# SolarArray1.net
KiCad netlist of a schematic drawn in Altium Designer
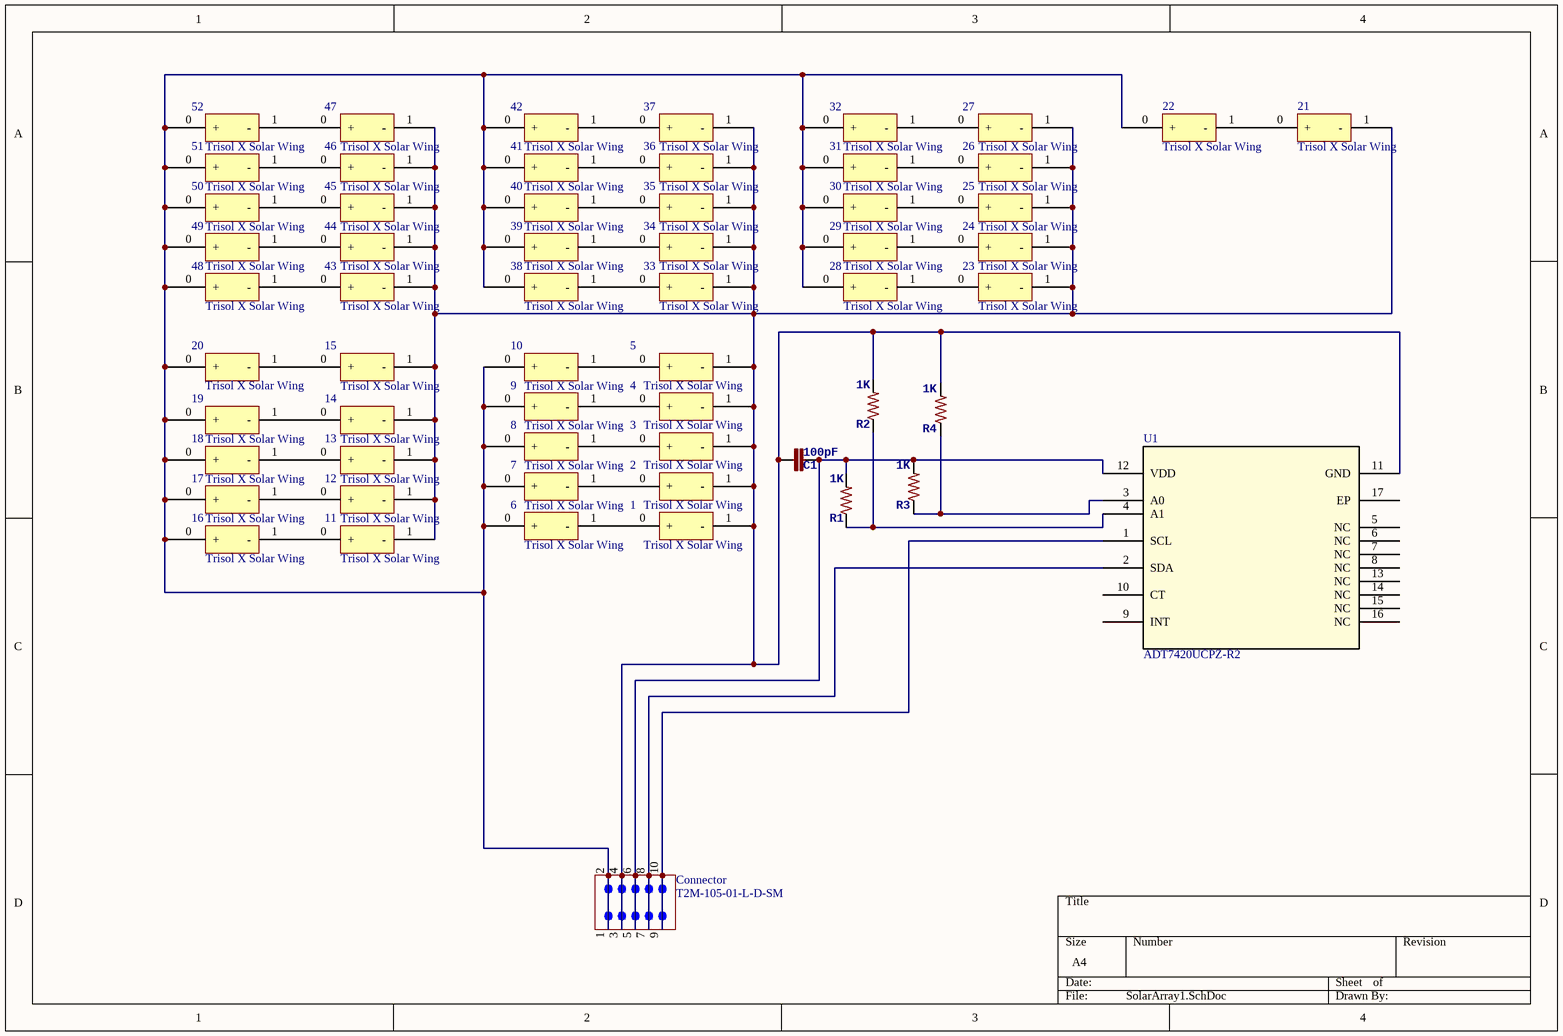
[diagram p0: SolarArray1.SchDoc]

(export (version "E")
  (design (tool "Eeschema 10.0.6"))
  (components
    (comp (ref "1")
      (value "Trisol X Solar Wing")
      (footprint "PCBComponent_1")
      (libsource (lib "CSDCPowerLib") (part "Trisol X Solar Wing"))
    )
    (comp (ref "2")
      (value "Trisol X Solar Wing")
      (footprint "PCBComponent_1")
      (libsource (lib "CSDCPowerLib") (part "Trisol X Solar Wing"))
    )
    (comp (ref "3")
      (value "Trisol X Solar Wing")
      (footprint "PCBComponent_1")
      (libsource (lib "CSDCPowerLib") (part "Trisol X Solar Wing"))
    )
    (comp (ref "4")
      (value "Trisol X Solar Wing")
      (footprint "PCBComponent_1")
      (libsource (lib "CSDCPowerLib") (part "Trisol X Solar Wing"))
    )
    (comp (ref "5")
      (value "Trisol X Solar Wing")
      (footprint "PCBComponent_1")
      (libsource (lib "CSDCPowerLib") (part "Trisol X Solar Wing"))
    )
    (comp (ref "6")
      (value "Trisol X Solar Wing")
      (footprint "PCBComponent_1")
      (libsource (lib "CSDCPowerLib") (part "Trisol X Solar Wing"))
    )
    (comp (ref "7")
      (value "Trisol X Solar Wing")
      (footprint "PCBComponent_1")
      (libsource (lib "CSDCPowerLib") (part "Trisol X Solar Wing"))
    )
    (comp (ref "8")
      (value "Trisol X Solar Wing")
      (footprint "PCBComponent_1")
      (libsource (lib "CSDCPowerLib") (part "Trisol X Solar Wing"))
    )
    (comp (ref "9")
      (value "Trisol X Solar Wing")
      (footprint "PCBComponent_1")
      (libsource (lib "CSDCPowerLib") (part "Trisol X Solar Wing"))
    )
    (comp (ref "10")
      (value "Trisol X Solar Wing")
      (footprint "PCBComponent_1")
      (libsource (lib "CSDCPowerLib") (part "Trisol X Solar Wing"))
    )
    (comp (ref "11")
      (value "Trisol X Solar Wing")
      (footprint "PCBComponent_1")
      (libsource (lib "CSDCPowerLib") (part "Trisol X Solar Wing"))
    )
    (comp (ref "12")
      (value "Trisol X Solar Wing")
      (footprint "PCBComponent_1")
      (libsource (lib "CSDCPowerLib") (part "Trisol X Solar Wing"))
    )
    (comp (ref "13")
      (value "Trisol X Solar Wing")
      (footprint "PCBComponent_1")
      (libsource (lib "CSDCPowerLib") (part "Trisol X Solar Wing"))
    )
    (comp (ref "14")
      (value "Trisol X Solar Wing")
      (footprint "PCBComponent_1")
      (libsource (lib "CSDCPowerLib") (part "Trisol X Solar Wing"))
    )
    (comp (ref "15")
      (value "Trisol X Solar Wing")
      (footprint "PCBComponent_1")
      (libsource (lib "CSDCPowerLib") (part "Trisol X Solar Wing"))
    )
    (comp (ref "16")
      (value "Trisol X Solar Wing")
      (footprint "PCBComponent_1")
      (libsource (lib "CSDCPowerLib") (part "Trisol X Solar Wing"))
    )
    (comp (ref "17")
      (value "Trisol X Solar Wing")
      (footprint "PCBComponent_1")
      (libsource (lib "CSDCPowerLib") (part "Trisol X Solar Wing"))
    )
    (comp (ref "18")
      (value "Trisol X Solar Wing")
      (footprint "PCBComponent_1")
      (libsource (lib "CSDCPowerLib") (part "Trisol X Solar Wing"))
    )
    (comp (ref "19")
      (value "Trisol X Solar Wing")
      (footprint "PCBComponent_1")
      (libsource (lib "CSDCPowerLib") (part "Trisol X Solar Wing"))
    )
    (comp (ref "20")
      (value "Trisol X Solar Wing")
      (footprint "PCBComponent_1")
      (libsource (lib "CSDCPowerLib") (part "Trisol X Solar Wing"))
    )
    (comp (ref "21")
      (value "Trisol X Solar Wing")
      (footprint "PCBComponent_1")
      (libsource (lib "CSDCPowerLib") (part "Trisol X Solar Wing"))
    )
    (comp (ref "22")
      (value "Trisol X Solar Wing")
      (footprint "PCBComponent_1")
      (libsource (lib "CSDCPowerLib") (part "Trisol X Solar Wing"))
    )
    (comp (ref "23")
      (value "Trisol X Solar Wing")
      (footprint "PCBComponent_1")
      (libsource (lib "CSDCPowerLib") (part "Trisol X Solar Wing"))
    )
    (comp (ref "24")
      (value "Trisol X Solar Wing")
      (footprint "PCBComponent_1")
      (libsource (lib "CSDCPowerLib") (part "Trisol X Solar Wing"))
    )
    (comp (ref "25")
      (value "Trisol X Solar Wing")
      (footprint "PCBComponent_1")
      (libsource (lib "CSDCPowerLib") (part "Trisol X Solar Wing"))
    )
    (comp (ref "26")
      (value "Trisol X Solar Wing")
      (footprint "PCBComponent_1")
      (libsource (lib "CSDCPowerLib") (part "Trisol X Solar Wing"))
    )
    (comp (ref "27")
      (value "Trisol X Solar Wing")
      (footprint "PCBComponent_1")
      (libsource (lib "CSDCPowerLib") (part "Trisol X Solar Wing"))
    )
    (comp (ref "28")
      (value "Trisol X Solar Wing")
      (footprint "PCBComponent_1")
      (libsource (lib "CSDCPowerLib") (part "Trisol X Solar Wing"))
    )
    (comp (ref "29")
      (value "Trisol X Solar Wing")
      (footprint "PCBComponent_1")
      (libsource (lib "CSDCPowerLib") (part "Trisol X Solar Wing"))
    )
    (comp (ref "30")
      (value "Trisol X Solar Wing")
      (footprint "PCBComponent_1")
      (libsource (lib "CSDCPowerLib") (part "Trisol X Solar Wing"))
    )
    (comp (ref "31")
      (value "Trisol X Solar Wing")
      (footprint "PCBComponent_1")
      (libsource (lib "CSDCPowerLib") (part "Trisol X Solar Wing"))
    )
    (comp (ref "32")
      (value "Trisol X Solar Wing")
      (footprint "PCBComponent_1")
      (libsource (lib "CSDCPowerLib") (part "Trisol X Solar Wing"))
    )
    (comp (ref "33")
      (value "Trisol X Solar Wing")
      (footprint "PCBComponent_1")
      (libsource (lib "CSDCPowerLib") (part "Trisol X Solar Wing"))
    )
    (comp (ref "34")
      (value "Trisol X Solar Wing")
      (footprint "PCBComponent_1")
      (libsource (lib "CSDCPowerLib") (part "Trisol X Solar Wing"))
    )
    (comp (ref "35")
      (value "Trisol X Solar Wing")
      (footprint "PCBComponent_1")
      (libsource (lib "CSDCPowerLib") (part "Trisol X Solar Wing"))
    )
    (comp (ref "36")
      (value "Trisol X Solar Wing")
      (footprint "PCBComponent_1")
      (libsource (lib "CSDCPowerLib") (part "Trisol X Solar Wing"))
    )
    (comp (ref "37")
      (value "Trisol X Solar Wing")
      (footprint "PCBComponent_1")
      (libsource (lib "CSDCPowerLib") (part "Trisol X Solar Wing"))
    )
    (comp (ref "38")
      (value "Trisol X Solar Wing")
      (footprint "PCBComponent_1")
      (libsource (lib "CSDCPowerLib") (part "Trisol X Solar Wing"))
    )
    (comp (ref "39")
      (value "Trisol X Solar Wing")
      (footprint "PCBComponent_1")
      (libsource (lib "CSDCPowerLib") (part "Trisol X Solar Wing"))
    )
    (comp (ref "40")
      (value "Trisol X Solar Wing")
      (footprint "PCBComponent_1")
      (libsource (lib "CSDCPowerLib") (part "Trisol X Solar Wing"))
    )
    (comp (ref "41")
      (value "Trisol X Solar Wing")
      (footprint "PCBComponent_1")
      (libsource (lib "CSDCPowerLib") (part "Trisol X Solar Wing"))
    )
    (comp (ref "42")
      (value "Trisol X Solar Wing")
      (footprint "PCBComponent_1")
      (libsource (lib "CSDCPowerLib") (part "Trisol X Solar Wing"))
    )
    (comp (ref "43")
      (value "Trisol X Solar Wing")
      (footprint "PCBComponent_1")
      (libsource (lib "CSDCPowerLib") (part "Trisol X Solar Wing"))
    )
    (comp (ref "44")
      (value "Trisol X Solar Wing")
      (footprint "PCBComponent_1")
      (libsource (lib "CSDCPowerLib") (part "Trisol X Solar Wing"))
    )
    (comp (ref "45")
      (value "Trisol X Solar Wing")
      (footprint "PCBComponent_1")
      (libsource (lib "CSDCPowerLib") (part "Trisol X Solar Wing"))
    )
    (comp (ref "46")
      (value "Trisol X Solar Wing")
      (footprint "PCBComponent_1")
      (libsource (lib "CSDCPowerLib") (part "Trisol X Solar Wing"))
    )
    (comp (ref "47")
      (value "Trisol X Solar Wing")
      (footprint "PCBComponent_1")
      (libsource (lib "CSDCPowerLib") (part "Trisol X Solar Wing"))
    )
    (comp (ref "48")
      (value "Trisol X Solar Wing")
      (footprint "PCBComponent_1")
      (libsource (lib "CSDCPowerLib") (part "Trisol X Solar Wing"))
    )
    (comp (ref "49")
      (value "Trisol X Solar Wing")
      (footprint "PCBComponent_1")
      (libsource (lib "CSDCPowerLib") (part "Trisol X Solar Wing"))
    )
    (comp (ref "50")
      (value "Trisol X Solar Wing")
      (footprint "PCBComponent_1")
      (libsource (lib "CSDCPowerLib") (part "Trisol X Solar Wing"))
    )
    (comp (ref "51")
      (value "Trisol X Solar Wing")
      (footprint "PCBComponent_1")
      (libsource (lib "CSDCPowerLib") (part "Trisol X Solar Wing"))
    )
    (comp (ref "52")
      (value "Trisol X Solar Wing")
      (footprint "PCBComponent_1")
      (libsource (lib "CSDCPowerLib") (part "Trisol X Solar Wing"))
    )
    (comp (ref "C1")
      (value "100pF")
      (footprint "0805")
      (fields (field (name "TOLERANCE") "±10%"))
      (libsource (lib "yusend_power") (part "CAP0805_1nF"))
    )
    (comp (ref "Connector")
      (value "T2M-105-01-L-D-SM")
      (footprint "T2M-105-01-X-D-SM")
      (libsource (lib "CSDCPowerLib") (part "T2M-105-01-X-D-SM"))
    )
    (comp (ref "R1")
      (value "1K")
      (footprint "0805")
      (fields
        (field (name "MANUFACTURER") "TE Connectivity")
        (field (name "MANUFACTURER PART NUMBER") "1625856-2")
        (field (name "TOLERANCE") "±10%")
      )
      (libsource (lib "yusend_power") (part "RESISTOR0805-RES_1K"))
    )
    (comp (ref "R2")
      (value "1K")
      (footprint "0805")
      (fields
        (field (name "MANUFACTURER") "TE Connectivity")
        (field (name "MANUFACTURER PART NUMBER") "1625856-2")
        (field (name "TOLERANCE") "±10%")
      )
      (libsource (lib "yusend_power") (part "RESISTOR0805-RES_1K"))
    )
    (comp (ref "R3")
      (value "1K")
      (footprint "0805")
      (fields
        (field (name "MANUFACTURER") "TE Connectivity")
        (field (name "MANUFACTURER PART NUMBER") "1625856-2")
        (field (name "TOLERANCE") "±10%")
      )
      (libsource (lib "yusend_power") (part "RESISTOR0805-RES_1K"))
    )
    (comp (ref "R4")
      (value "1K")
      (footprint "0805")
      (fields
        (field (name "MANUFACTURER") "TE Connectivity")
        (field (name "MANUFACTURER PART NUMBER") "1625856-2")
        (field (name "TOLERANCE") "±10%")
      )
      (libsource (lib "yusend_power") (part "RESISTOR0805-RES_1K"))
    )
    (comp (ref "U1")
      (value "ADT7420UCPZ-R2")
      (footprint "CP_16_17")
      (description "Imported")
      (libsource (lib "Temperature sensor") (part "ADT7420UCPZ-R2"))
    )
  )
  (nets
    (net (code "1") (name "Net-(1-+)") (class "Default")
      (node (ref "1") (pin "0") (pinfunction "+_0") (pintype "passive"))
      (node (ref "6") (pin "1") (pinfunction "-_1") (pintype "passive"))
    )
    (net (code "2") (name "Net-(1--)") (class "Default")
      (node (ref "1") (pin "1") (pinfunction "-_1") (pintype "passive"))
      (node (ref "11") (pin "1") (pinfunction "-_1") (pintype "passive"))
      (node (ref "12") (pin "1") (pinfunction "-_1") (pintype "passive"))
      (node (ref "13") (pin "1") (pinfunction "-_1") (pintype "passive"))
      (node (ref "14") (pin "1") (pinfunction "-_1") (pintype "passive"))
      (node (ref "15") (pin "1") (pinfunction "-_1") (pintype "passive"))
      (node (ref "2") (pin "1") (pinfunction "-_1") (pintype "passive"))
      (node (ref "21") (pin "1") (pinfunction "-_1") (pintype "passive"))
      (node (ref "23") (pin "1") (pinfunction "-_1") (pintype "passive"))
      (node (ref "24") (pin "1") (pinfunction "-_1") (pintype "passive"))
      (node (ref "25") (pin "1") (pinfunction "-_1") (pintype "passive"))
      (node (ref "26") (pin "1") (pinfunction "-_1") (pintype "passive"))
      (node (ref "27") (pin "1") (pinfunction "-_1") (pintype "passive"))
      (node (ref "3") (pin "1") (pinfunction "-_1") (pintype "passive"))
      (node (ref "33") (pin "1") (pinfunction "-_1") (pintype "passive"))
      (node (ref "34") (pin "1") (pinfunction "-_1") (pintype "passive"))
      (node (ref "35") (pin "1") (pinfunction "-_1") (pintype "passive"))
      (node (ref "36") (pin "1") (pinfunction "-_1") (pintype "passive"))
      (node (ref "37") (pin "1") (pinfunction "-_1") (pintype "passive"))
      (node (ref "4") (pin "1") (pinfunction "-_1") (pintype "passive"))
      (node (ref "43") (pin "1") (pinfunction "-_1") (pintype "passive"))
      (node (ref "44") (pin "1") (pinfunction "-_1") (pintype "passive"))
      (node (ref "45") (pin "1") (pinfunction "-_1") (pintype "passive"))
      (node (ref "46") (pin "1") (pinfunction "-_1") (pintype "passive"))
      (node (ref "47") (pin "1") (pinfunction "-_1") (pintype "passive"))
      (node (ref "5") (pin "1") (pinfunction "-_1") (pintype "passive"))
      (node (ref "C1") (pin "1") (pinfunction "1_1") (pintype "passive"))
      (node (ref "Connector") (pin "3") (pinfunction "PINLENGTH=20_3") (pintype "passive"))
      (node (ref "Connector") (pin "4") (pinfunction "PINLENGTH=20_4") (pintype "passive"))
      (node (ref "R2") (pin "2") (pinfunction "2_2") (pintype "passive"))
      (node (ref "R4") (pin "2") (pinfunction "2_2") (pintype "passive"))
      (node (ref "U1") (pin "11") (pinfunction "GND_11") (pintype "passive"))
    )
    (net (code "3") (name "Net-(2-+)") (class "Default")
      (node (ref "2") (pin "0") (pinfunction "+_0") (pintype "passive"))
      (node (ref "7") (pin "1") (pinfunction "-_1") (pintype "passive"))
    )
    (net (code "4") (name "Net-(3-+)") (class "Default")
      (node (ref "3") (pin "0") (pinfunction "+_0") (pintype "passive"))
      (node (ref "8") (pin "1") (pinfunction "-_1") (pintype "passive"))
    )
    (net (code "5") (name "Net-(4-+)") (class "Default")
      (node (ref "4") (pin "0") (pinfunction "+_0") (pintype "passive"))
      (node (ref "9") (pin "1") (pinfunction "-_1") (pintype "passive"))
    )
    (net (code "6") (name "Net-(10-+)") (class "Default")
      (node (ref "10") (pin "0") (pinfunction "+_0") (pintype "passive"))
      (node (ref "16") (pin "0") (pinfunction "+_0") (pintype "passive"))
      (node (ref "17") (pin "0") (pinfunction "+_0") (pintype "passive"))
      (node (ref "18") (pin "0") (pinfunction "+_0") (pintype "passive"))
      (node (ref "19") (pin "0") (pinfunction "+_0") (pintype "passive"))
      (node (ref "20") (pin "0") (pinfunction "+_0") (pintype "passive"))
      (node (ref "22") (pin "0") (pinfunction "+_0") (pintype "passive"))
      (node (ref "28") (pin "0") (pinfunction "+_0") (pintype "passive"))
      (node (ref "29") (pin "0") (pinfunction "+_0") (pintype "passive"))
      (node (ref "30") (pin "0") (pinfunction "+_0") (pintype "passive"))
      (node (ref "31") (pin "0") (pinfunction "+_0") (pintype "passive"))
      (node (ref "32") (pin "0") (pinfunction "+_0") (pintype "passive"))
      (node (ref "38") (pin "0") (pinfunction "+_0") (pintype "passive"))
      (node (ref "39") (pin "0") (pinfunction "+_0") (pintype "passive"))
      (node (ref "40") (pin "0") (pinfunction "+_0") (pintype "passive"))
      (node (ref "41") (pin "0") (pinfunction "+_0") (pintype "passive"))
      (node (ref "42") (pin "0") (pinfunction "+_0") (pintype "passive"))
      (node (ref "48") (pin "0") (pinfunction "+_0") (pintype "passive"))
      (node (ref "49") (pin "0") (pinfunction "+_0") (pintype "passive"))
      (node (ref "50") (pin "0") (pinfunction "+_0") (pintype "passive"))
      (node (ref "51") (pin "0") (pinfunction "+_0") (pintype "passive"))
      (node (ref "52") (pin "0") (pinfunction "+_0") (pintype "passive"))
      (node (ref "6") (pin "0") (pinfunction "+_0") (pintype "passive"))
      (node (ref "7") (pin "0") (pinfunction "+_0") (pintype "passive"))
      (node (ref "8") (pin "0") (pinfunction "+_0") (pintype "passive"))
      (node (ref "9") (pin "0") (pinfunction "+_0") (pintype "passive"))
      (node (ref "Connector") (pin "1") (pinfunction "PINLENGTH=20_1") (pintype "passive"))
      (node (ref "Connector") (pin "2") (pinfunction "PINLENGTH=20_2") (pintype "passive"))
    )
    (net (code "7") (name "Net-(10--)") (class "Default")
      (node (ref "10") (pin "1") (pinfunction "-_1") (pintype "passive"))
      (node (ref "5") (pin "0") (pinfunction "+_0") (pintype "passive"))
    )
    (net (code "8") (name "Net-(11-+)") (class "Default")
      (node (ref "11") (pin "0") (pinfunction "+_0") (pintype "passive"))
      (node (ref "16") (pin "1") (pinfunction "-_1") (pintype "passive"))
    )
    (net (code "9") (name "Net-(12-+)") (class "Default")
      (node (ref "12") (pin "0") (pinfunction "+_0") (pintype "passive"))
      (node (ref "17") (pin "1") (pinfunction "-_1") (pintype "passive"))
    )
    (net (code "10") (name "Net-(13-+)") (class "Default")
      (node (ref "13") (pin "0") (pinfunction "+_0") (pintype "passive"))
      (node (ref "18") (pin "1") (pinfunction "-_1") (pintype "passive"))
    )
    (net (code "11") (name "Net-(14-+)") (class "Default")
      (node (ref "14") (pin "0") (pinfunction "+_0") (pintype "passive"))
      (node (ref "19") (pin "1") (pinfunction "-_1") (pintype "passive"))
    )
    (net (code "12") (name "Net-(15-+)") (class "Default")
      (node (ref "15") (pin "0") (pinfunction "+_0") (pintype "passive"))
      (node (ref "20") (pin "1") (pinfunction "-_1") (pintype "passive"))
    )
    (net (code "13") (name "Net-(21-+)") (class "Default")
      (node (ref "21") (pin "0") (pinfunction "+_0") (pintype "passive"))
      (node (ref "22") (pin "1") (pinfunction "-_1") (pintype "passive"))
    )
    (net (code "14") (name "Net-(23-+)") (class "Default")
      (node (ref "23") (pin "0") (pinfunction "+_0") (pintype "passive"))
      (node (ref "28") (pin "1") (pinfunction "-_1") (pintype "passive"))
    )
    (net (code "15") (name "Net-(24-+)") (class "Default")
      (node (ref "24") (pin "0") (pinfunction "+_0") (pintype "passive"))
      (node (ref "29") (pin "1") (pinfunction "-_1") (pintype "passive"))
    )
    (net (code "16") (name "Net-(25-+)") (class "Default")
      (node (ref "25") (pin "0") (pinfunction "+_0") (pintype "passive"))
      (node (ref "30") (pin "1") (pinfunction "-_1") (pintype "passive"))
    )
    (net (code "17") (name "Net-(26-+)") (class "Default")
      (node (ref "26") (pin "0") (pinfunction "+_0") (pintype "passive"))
      (node (ref "31") (pin "1") (pinfunction "-_1") (pintype "passive"))
    )
    (net (code "18") (name "Net-(27-+)") (class "Default")
      (node (ref "27") (pin "0") (pinfunction "+_0") (pintype "passive"))
      (node (ref "32") (pin "1") (pinfunction "-_1") (pintype "passive"))
    )
    (net (code "19") (name "Net-(33-+)") (class "Default")
      (node (ref "33") (pin "0") (pinfunction "+_0") (pintype "passive"))
      (node (ref "38") (pin "1") (pinfunction "-_1") (pintype "passive"))
    )
    (net (code "20") (name "Net-(34-+)") (class "Default")
      (node (ref "34") (pin "0") (pinfunction "+_0") (pintype "passive"))
      (node (ref "39") (pin "1") (pinfunction "-_1") (pintype "passive"))
    )
    (net (code "21") (name "Net-(35-+)") (class "Default")
      (node (ref "35") (pin "0") (pinfunction "+_0") (pintype "passive"))
      (node (ref "40") (pin "1") (pinfunction "-_1") (pintype "passive"))
    )
    (net (code "22") (name "Net-(36-+)") (class "Default")
      (node (ref "36") (pin "0") (pinfunction "+_0") (pintype "passive"))
      (node (ref "41") (pin "1") (pinfunction "-_1") (pintype "passive"))
    )
    (net (code "23") (name "Net-(37-+)") (class "Default")
      (node (ref "37") (pin "0") (pinfunction "+_0") (pintype "passive"))
      (node (ref "42") (pin "1") (pinfunction "-_1") (pintype "passive"))
    )
    (net (code "24") (name "Net-(43-+)") (class "Default")
      (node (ref "43") (pin "0") (pinfunction "+_0") (pintype "passive"))
      (node (ref "48") (pin "1") (pinfunction "-_1") (pintype "passive"))
    )
    (net (code "25") (name "Net-(44-+)") (class "Default")
      (node (ref "44") (pin "0") (pinfunction "+_0") (pintype "passive"))
      (node (ref "49") (pin "1") (pinfunction "-_1") (pintype "passive"))
    )
    (net (code "26") (name "Net-(45-+)") (class "Default")
      (node (ref "45") (pin "0") (pinfunction "+_0") (pintype "passive"))
      (node (ref "50") (pin "1") (pinfunction "-_1") (pintype "passive"))
    )
    (net (code "27") (name "Net-(46-+)") (class "Default")
      (node (ref "46") (pin "0") (pinfunction "+_0") (pintype "passive"))
      (node (ref "51") (pin "1") (pinfunction "-_1") (pintype "passive"))
    )
    (net (code "28") (name "Net-(47-+)") (class "Default")
      (node (ref "47") (pin "0") (pinfunction "+_0") (pintype "passive"))
      (node (ref "52") (pin "1") (pinfunction "-_1") (pintype "passive"))
    )
    (net (code "29") (name "Net-(U1-A0)") (class "Default")
      (node (ref "R3") (pin "1") (pinfunction "1_1") (pintype "passive"))
      (node (ref "R4") (pin "1") (pinfunction "1_1") (pintype "passive"))
      (node (ref "U1") (pin "3") (pinfunction "A0_3") (pintype "passive"))
    )
    (net (code "30") (name "Net-(U1-A1)") (class "Default")
      (node (ref "R1") (pin "1") (pinfunction "1_1") (pintype "passive"))
      (node (ref "R2") (pin "1") (pinfunction "1_1") (pintype "passive"))
      (node (ref "U1") (pin "4") (pinfunction "A1_4") (pintype "passive"))
    )
    (net (code "31") (name "Net-(U1-SCL)") (class "Default")
      (node (ref "Connector") (pin "10") (pinfunction "PINLENGTH=20_10") (pintype "passive"))
      (node (ref "Connector") (pin "9") (pinfunction "PINLENGTH=20_9") (pintype "passive"))
      (node (ref "U1") (pin "1") (pinfunction "SCL_1") (pintype "passive"))
    )
    (net (code "32") (name "Net-(U1-SDA)") (class "Default")
      (node (ref "Connector") (pin "7") (pinfunction "PINLENGTH=20_7") (pintype "passive"))
      (node (ref "Connector") (pin "8") (pinfunction "PINLENGTH=20_8") (pintype "passive"))
      (node (ref "U1") (pin "2") (pinfunction "SDA_2") (pintype "passive"))
    )
    (net (code "33") (name "Net-(U1-VDD)") (class "Default")
      (node (ref "C1") (pin "2") (pinfunction "2_2") (pintype "passive"))
      (node (ref "Connector") (pin "5") (pinfunction "PINLENGTH=20_5") (pintype "passive"))
      (node (ref "Connector") (pin "6") (pinfunction "PINLENGTH=20_6") (pintype "passive"))
      (node (ref "R1") (pin "2") (pinfunction "2_2") (pintype "passive"))
      (node (ref "R3") (pin "2") (pinfunction "2_2") (pintype "passive"))
      (node (ref "U1") (pin "12") (pinfunction "VDD_12") (pintype "passive"))
    )
    (net (code "34") (name "unconnected-(U1-CT-Pad10)") (class "Default")
      (node (ref "U1") (pin "10") (pinfunction "CT_10") (pintype "passive"))
    )
    (net (code "35") (name "unconnected-(U1-EP-Pad17)") (class "Default")
      (node (ref "U1") (pin "17") (pinfunction "EP_17") (pintype "passive"))
    )
    (net (code "36") (name "unconnected-(U1-INT-Pad9)") (class "Default")
      (node (ref "U1") (pin "9") (pinfunction "INT_9") (pintype "passive"))
    )
    (net (code "37") (name "unconnected-(U1-NC-Pad5)") (class "Default")
      (node (ref "U1") (pin "5") (pinfunction "NC_5") (pintype "passive"))
    )
    (net (code "38") (name "unconnected-(U1-NC-Pad6)") (class "Default")
      (node (ref "U1") (pin "6") (pinfunction "NC_6") (pintype "passive"))
    )
    (net (code "39") (name "unconnected-(U1-NC-Pad7)") (class "Default")
      (node (ref "U1") (pin "7") (pinfunction "NC_7") (pintype "passive"))
    )
    (net (code "40") (name "unconnected-(U1-NC-Pad8)") (class "Default")
      (node (ref "U1") (pin "8") (pinfunction "NC_8") (pintype "passive"))
    )
    (net (code "41") (name "unconnected-(U1-NC-Pad13)") (class "Default")
      (node (ref "U1") (pin "13") (pinfunction "NC_13") (pintype "passive"))
    )
    (net (code "42") (name "unconnected-(U1-NC-Pad14)") (class "Default")
      (node (ref "U1") (pin "14") (pinfunction "NC_14") (pintype "passive"))
    )
    (net (code "43") (name "unconnected-(U1-NC-Pad15)") (class "Default")
      (node (ref "U1") (pin "15") (pinfunction "NC_15") (pintype "passive"))
    )
    (net (code "44") (name "unconnected-(U1-NC-Pad16)") (class "Default")
      (node (ref "U1") (pin "16") (pinfunction "NC_16") (pintype "passive"))
    )
  )
)
